# B117C.net
KiCad netlist of a schematic drawn in EAGLE
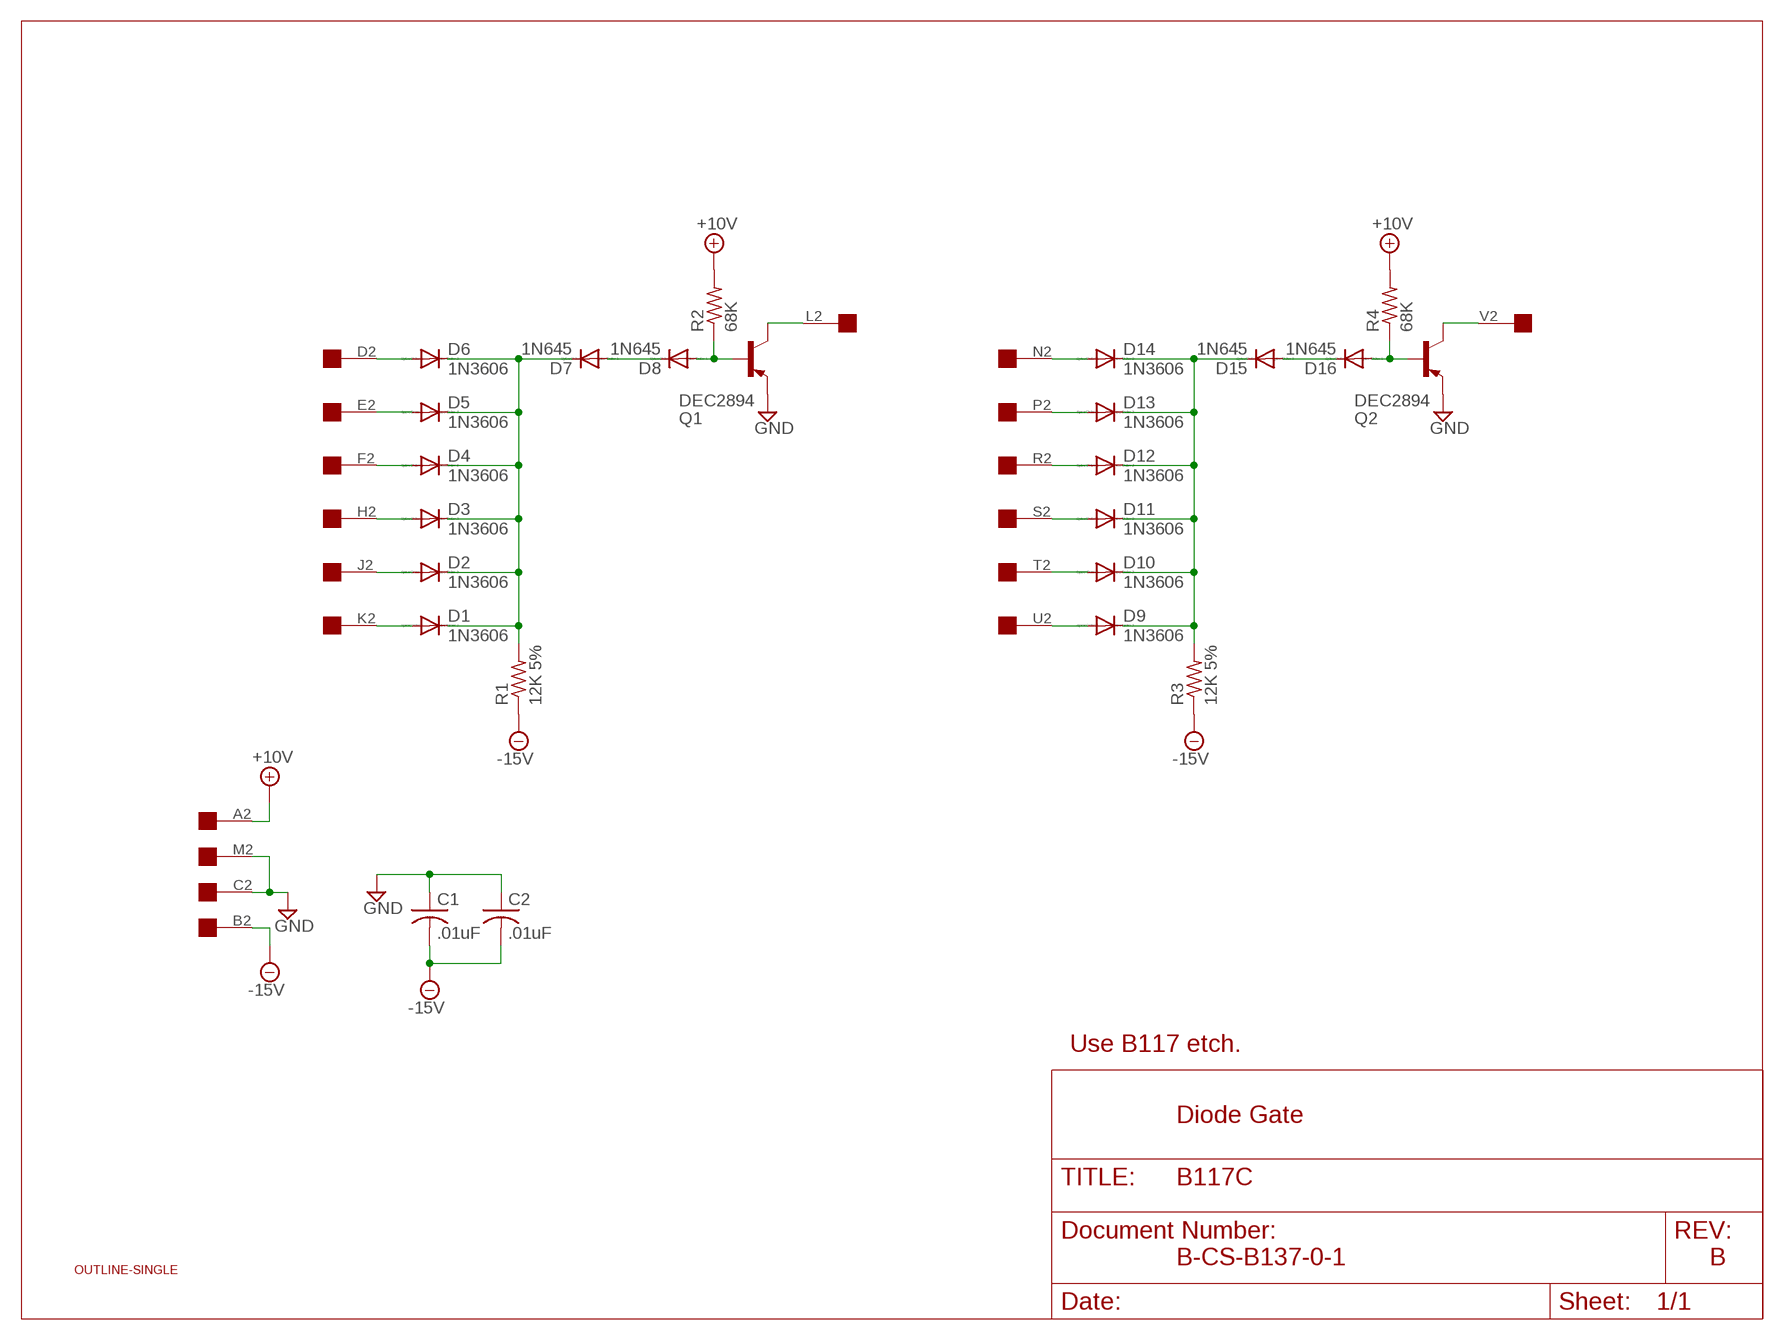
[diagram p0: schematic, sheet 1]

(export (version "E")
  (design (tool "Eeschema 10.0.6"))
  (components
    (comp (ref "C1")
      (value ".01uF")
      (footprint "eagle-import:C050-025X075")
      (libsource (lib "eagle-import") (part "C-US050-025X075"))
    )
    (comp (ref "C2")
      (value ".01uF")
      (footprint "eagle-import:C050-025X075")
      (libsource (lib "eagle-import") (part "C-US050-025X075"))
    )
    (comp (ref "D1")
      (value "1N3606")
      (footprint "eagle-import:DO35-10")
      (libsource (lib "eagle-import") (part "DIODE-DO35-10"))
    )
    (comp (ref "D2")
      (value "1N3606")
      (footprint "eagle-import:DO35-10")
      (libsource (lib "eagle-import") (part "DIODE-DO35-10"))
    )
    (comp (ref "D3")
      (value "1N3606")
      (footprint "eagle-import:DO35-10")
      (libsource (lib "eagle-import") (part "DIODE-DO35-10"))
    )
    (comp (ref "D4")
      (value "1N3606")
      (footprint "eagle-import:DO35-10")
      (libsource (lib "eagle-import") (part "DIODE-DO35-10"))
    )
    (comp (ref "D5")
      (value "1N3606")
      (footprint "eagle-import:DO35-10")
      (libsource (lib "eagle-import") (part "DIODE-DO35-10"))
    )
    (comp (ref "D6")
      (value "1N3606")
      (footprint "eagle-import:DO35-10")
      (libsource (lib "eagle-import") (part "DIODE-DO35-10"))
    )
    (comp (ref "D7")
      (value "1N645")
      (footprint "eagle-import:DO35-10")
      (libsource (lib "eagle-import") (part "DIODE-DO35-10"))
    )
    (comp (ref "D8")
      (value "1N645")
      (footprint "eagle-import:DO35-10")
      (libsource (lib "eagle-import") (part "DIODE-DO35-10"))
    )
    (comp (ref "D9")
      (value "1N3606")
      (footprint "eagle-import:DO35-10")
      (libsource (lib "eagle-import") (part "DIODE-DO35-10"))
    )
    (comp (ref "D10")
      (value "1N3606")
      (footprint "eagle-import:DO35-10")
      (libsource (lib "eagle-import") (part "DIODE-DO35-10"))
    )
    (comp (ref "D11")
      (value "1N3606")
      (footprint "eagle-import:DO35-10")
      (libsource (lib "eagle-import") (part "DIODE-DO35-10"))
    )
    (comp (ref "D12")
      (value "1N3606")
      (footprint "eagle-import:DO35-10")
      (libsource (lib "eagle-import") (part "DIODE-DO35-10"))
    )
    (comp (ref "D13")
      (value "1N3606")
      (footprint "eagle-import:DO35-10")
      (libsource (lib "eagle-import") (part "DIODE-DO35-10"))
    )
    (comp (ref "D14")
      (value "1N3606")
      (footprint "eagle-import:DO35-10")
      (libsource (lib "eagle-import") (part "DIODE-DO35-10"))
    )
    (comp (ref "D15")
      (value "1N645")
      (footprint "eagle-import:DO35-10")
      (libsource (lib "eagle-import") (part "DIODE-DO35-10"))
    )
    (comp (ref "D16")
      (value "1N645")
      (footprint "eagle-import:DO35-10")
      (libsource (lib "eagle-import") (part "DIODE-DO35-10"))
    )
    (comp (ref "Q1")
      (value "DEC2894")
      (footprint "eagle-import:TO5")
      (libsource (lib "eagle-import") (part "-PNP-TO5"))
    )
    (comp (ref "Q2")
      (value "DEC2894")
      (footprint "eagle-import:TO5")
      (libsource (lib "eagle-import") (part "-PNP-TO5"))
    )
    (comp (ref "R1")
      (value "12K 5%")
      (footprint "eagle-import:0207_10")
      (libsource (lib "eagle-import") (part "R-US_0207/10"))
    )
    (comp (ref "R2")
      (value "68K")
      (footprint "eagle-import:0207_10")
      (libsource (lib "eagle-import") (part "R-US_0207/10"))
    )
    (comp (ref "R3")
      (value "12K 5%")
      (footprint "eagle-import:0207_10")
      (libsource (lib "eagle-import") (part "R-US_0207/10"))
    )
    (comp (ref "R4")
      (value "68K")
      (footprint "eagle-import:0207_10")
      (libsource (lib "eagle-import") (part "R-US_0207/10"))
    )
    (comp (ref "U$1")
      (value "OUTLINE-SINGLE")
      (footprint "eagle-import:SINGLE")
      (libsource (lib "eagle-import") (part "OUTLINE-SINGLE"))
    )
    (comp (ref "U$2")
      (value "EDGE-1")
      (footprint "eagle-import:EDGE-CON1")
      (libsource (lib "eagle-import") (part "EDGE-1"))
    )
  )
  (nets
    (net (code "1") (name "+10V") (class "Default")
      (node (ref "R2") (pin "2") (pinfunction "2_2") (pintype "passive"))
      (node (ref "R4") (pin "2") (pinfunction "2_2") (pintype "passive"))
      (node (ref "U$2") (pin "A2") (pinfunction "1_A2") (pintype "bidirectional"))
    )
    (net (code "2") (name "-15V") (class "Default")
      (node (ref "C1") (pin "2") (pinfunction "2_2") (pintype "passive"))
      (node (ref "C2") (pin "2") (pinfunction "2_2") (pintype "passive"))
      (node (ref "R1") (pin "1") (pinfunction "1_1") (pintype "passive"))
      (node (ref "R3") (pin "1") (pinfunction "1_1") (pintype "passive"))
      (node (ref "U$2") (pin "B2") (pinfunction "1_B2") (pintype "bidirectional"))
    )
    (net (code "3") (name "GND") (class "Default")
      (node (ref "C1") (pin "1") (pinfunction "1_1") (pintype "passive"))
      (node (ref "C2") (pin "1") (pinfunction "1_1") (pintype "passive"))
      (node (ref "Q1") (pin "1") (pinfunction "E_1") (pintype "passive"))
      (node (ref "Q2") (pin "1") (pinfunction "E_1") (pintype "passive"))
      (node (ref "U$2") (pin "C2") (pinfunction "1_C2") (pintype "bidirectional"))
      (node (ref "U$2") (pin "M2") (pinfunction "1_M2") (pintype "bidirectional"))
    )
    (net (code "4") (name "Net-(D1-PadC)") (class "Default")
      (node (ref "D1") (pin "C") (pinfunction "C_C") (pintype "passive"))
      (node (ref "D2") (pin "C") (pinfunction "C_C") (pintype "passive"))
      (node (ref "D3") (pin "C") (pinfunction "C_C") (pintype "passive"))
      (node (ref "D4") (pin "C") (pinfunction "C_C") (pintype "passive"))
      (node (ref "D5") (pin "C") (pinfunction "C_C") (pintype "passive"))
      (node (ref "D6") (pin "C") (pinfunction "C_C") (pintype "passive"))
      (node (ref "D7") (pin "C") (pinfunction "C_C") (pintype "passive"))
      (node (ref "R1") (pin "2") (pinfunction "2_2") (pintype "passive"))
    )
    (net (code "5") (name "Net-(D7-PadA)") (class "Default")
      (node (ref "D7") (pin "A") (pinfunction "A_A") (pintype "passive"))
      (node (ref "D8") (pin "C") (pinfunction "C_C") (pintype "passive"))
    )
    (net (code "6") (name "Net-(D10-PadC)") (class "Default")
      (node (ref "D10") (pin "C") (pinfunction "C_C") (pintype "passive"))
      (node (ref "D11") (pin "C") (pinfunction "C_C") (pintype "passive"))
      (node (ref "D12") (pin "C") (pinfunction "C_C") (pintype "passive"))
      (node (ref "D13") (pin "C") (pinfunction "C_C") (pintype "passive"))
      (node (ref "D14") (pin "C") (pinfunction "C_C") (pintype "passive"))
      (node (ref "D15") (pin "C") (pinfunction "C_C") (pintype "passive"))
      (node (ref "D9") (pin "C") (pinfunction "C_C") (pintype "passive"))
      (node (ref "R3") (pin "2") (pinfunction "2_2") (pintype "passive"))
    )
    (net (code "7") (name "Net-(D15-PadA)") (class "Default")
      (node (ref "D15") (pin "A") (pinfunction "A_A") (pintype "passive"))
      (node (ref "D16") (pin "C") (pinfunction "C_C") (pintype "passive"))
    )
    (net (code "8") (name "Net-(Q1-B)") (class "Default")
      (node (ref "D8") (pin "A") (pinfunction "A_A") (pintype "passive"))
      (node (ref "Q1") (pin "2") (pinfunction "B_2") (pintype "passive"))
      (node (ref "R2") (pin "1") (pinfunction "1_1") (pintype "passive"))
    )
    (net (code "9") (name "Net-(Q1-C)") (class "Default")
      (node (ref "Q1") (pin "3") (pinfunction "C_3") (pintype "passive"))
      (node (ref "U$2") (pin "L2") (pinfunction "1_L2") (pintype "bidirectional"))
    )
    (net (code "10") (name "Net-(Q2-B)") (class "Default")
      (node (ref "D16") (pin "A") (pinfunction "A_A") (pintype "passive"))
      (node (ref "Q2") (pin "2") (pinfunction "B_2") (pintype "passive"))
      (node (ref "R4") (pin "1") (pinfunction "1_1") (pintype "passive"))
    )
    (net (code "11") (name "Net-(Q2-C)") (class "Default")
      (node (ref "Q2") (pin "3") (pinfunction "C_3") (pintype "passive"))
      (node (ref "U$2") (pin "V2") (pinfunction "1_V2") (pintype "bidirectional"))
    )
    (net (code "12") (name "Net-(U$2D-1)") (class "Default")
      (node (ref "D6") (pin "A") (pinfunction "A_A") (pintype "passive"))
      (node (ref "U$2") (pin "D2") (pinfunction "1_D2") (pintype "bidirectional"))
    )
    (net (code "13") (name "Net-(U$2E-1)") (class "Default")
      (node (ref "D5") (pin "A") (pinfunction "A_A") (pintype "passive"))
      (node (ref "U$2") (pin "E2") (pinfunction "1_E2") (pintype "bidirectional"))
    )
    (net (code "14") (name "Net-(U$2F-1)") (class "Default")
      (node (ref "D4") (pin "A") (pinfunction "A_A") (pintype "passive"))
      (node (ref "U$2") (pin "F2") (pinfunction "1_F2") (pintype "bidirectional"))
    )
    (net (code "15") (name "Net-(U$2G-1)") (class "Default")
      (node (ref "D3") (pin "A") (pinfunction "A_A") (pintype "passive"))
      (node (ref "U$2") (pin "H2") (pinfunction "1_H2") (pintype "bidirectional"))
    )
    (net (code "16") (name "Net-(U$2H-1)") (class "Default")
      (node (ref "D2") (pin "A") (pinfunction "A_A") (pintype "passive"))
      (node (ref "U$2") (pin "J2") (pinfunction "1_J2") (pintype "bidirectional"))
    )
    (net (code "17") (name "Net-(U$2I-1)") (class "Default")
      (node (ref "D1") (pin "A") (pinfunction "A_A") (pintype "passive"))
      (node (ref "U$2") (pin "K2") (pinfunction "1_K2") (pintype "bidirectional"))
    )
    (net (code "18") (name "Net-(U$2L-1)") (class "Default")
      (node (ref "D14") (pin "A") (pinfunction "A_A") (pintype "passive"))
      (node (ref "U$2") (pin "N2") (pinfunction "1_N2") (pintype "bidirectional"))
    )
    (net (code "19") (name "Net-(U$2M-1)") (class "Default")
      (node (ref "D13") (pin "A") (pinfunction "A_A") (pintype "passive"))
      (node (ref "U$2") (pin "P2") (pinfunction "1_P2") (pintype "bidirectional"))
    )
    (net (code "20") (name "Net-(U$2N-1)") (class "Default")
      (node (ref "D12") (pin "A") (pinfunction "A_A") (pintype "passive"))
      (node (ref "U$2") (pin "R2") (pinfunction "1_R2") (pintype "bidirectional"))
    )
    (net (code "21") (name "Net-(U$2O-1)") (class "Default")
      (node (ref "D11") (pin "A") (pinfunction "A_A") (pintype "passive"))
      (node (ref "U$2") (pin "S2") (pinfunction "1_S2") (pintype "bidirectional"))
    )
    (net (code "22") (name "Net-(U$2P-1)") (class "Default")
      (node (ref "D10") (pin "A") (pinfunction "A_A") (pintype "passive"))
      (node (ref "U$2") (pin "T2") (pinfunction "1_T2") (pintype "bidirectional"))
    )
    (net (code "23") (name "Net-(U$2Q-1)") (class "Default")
      (node (ref "D9") (pin "A") (pinfunction "A_A") (pintype "passive"))
      (node (ref "U$2") (pin "U2") (pinfunction "1_U2") (pintype "bidirectional"))
    )
  )
)
